# ZYNQ_JTAG_and_Decoupling.net
KiCad netlist of a schematic drawn in Altium Designer
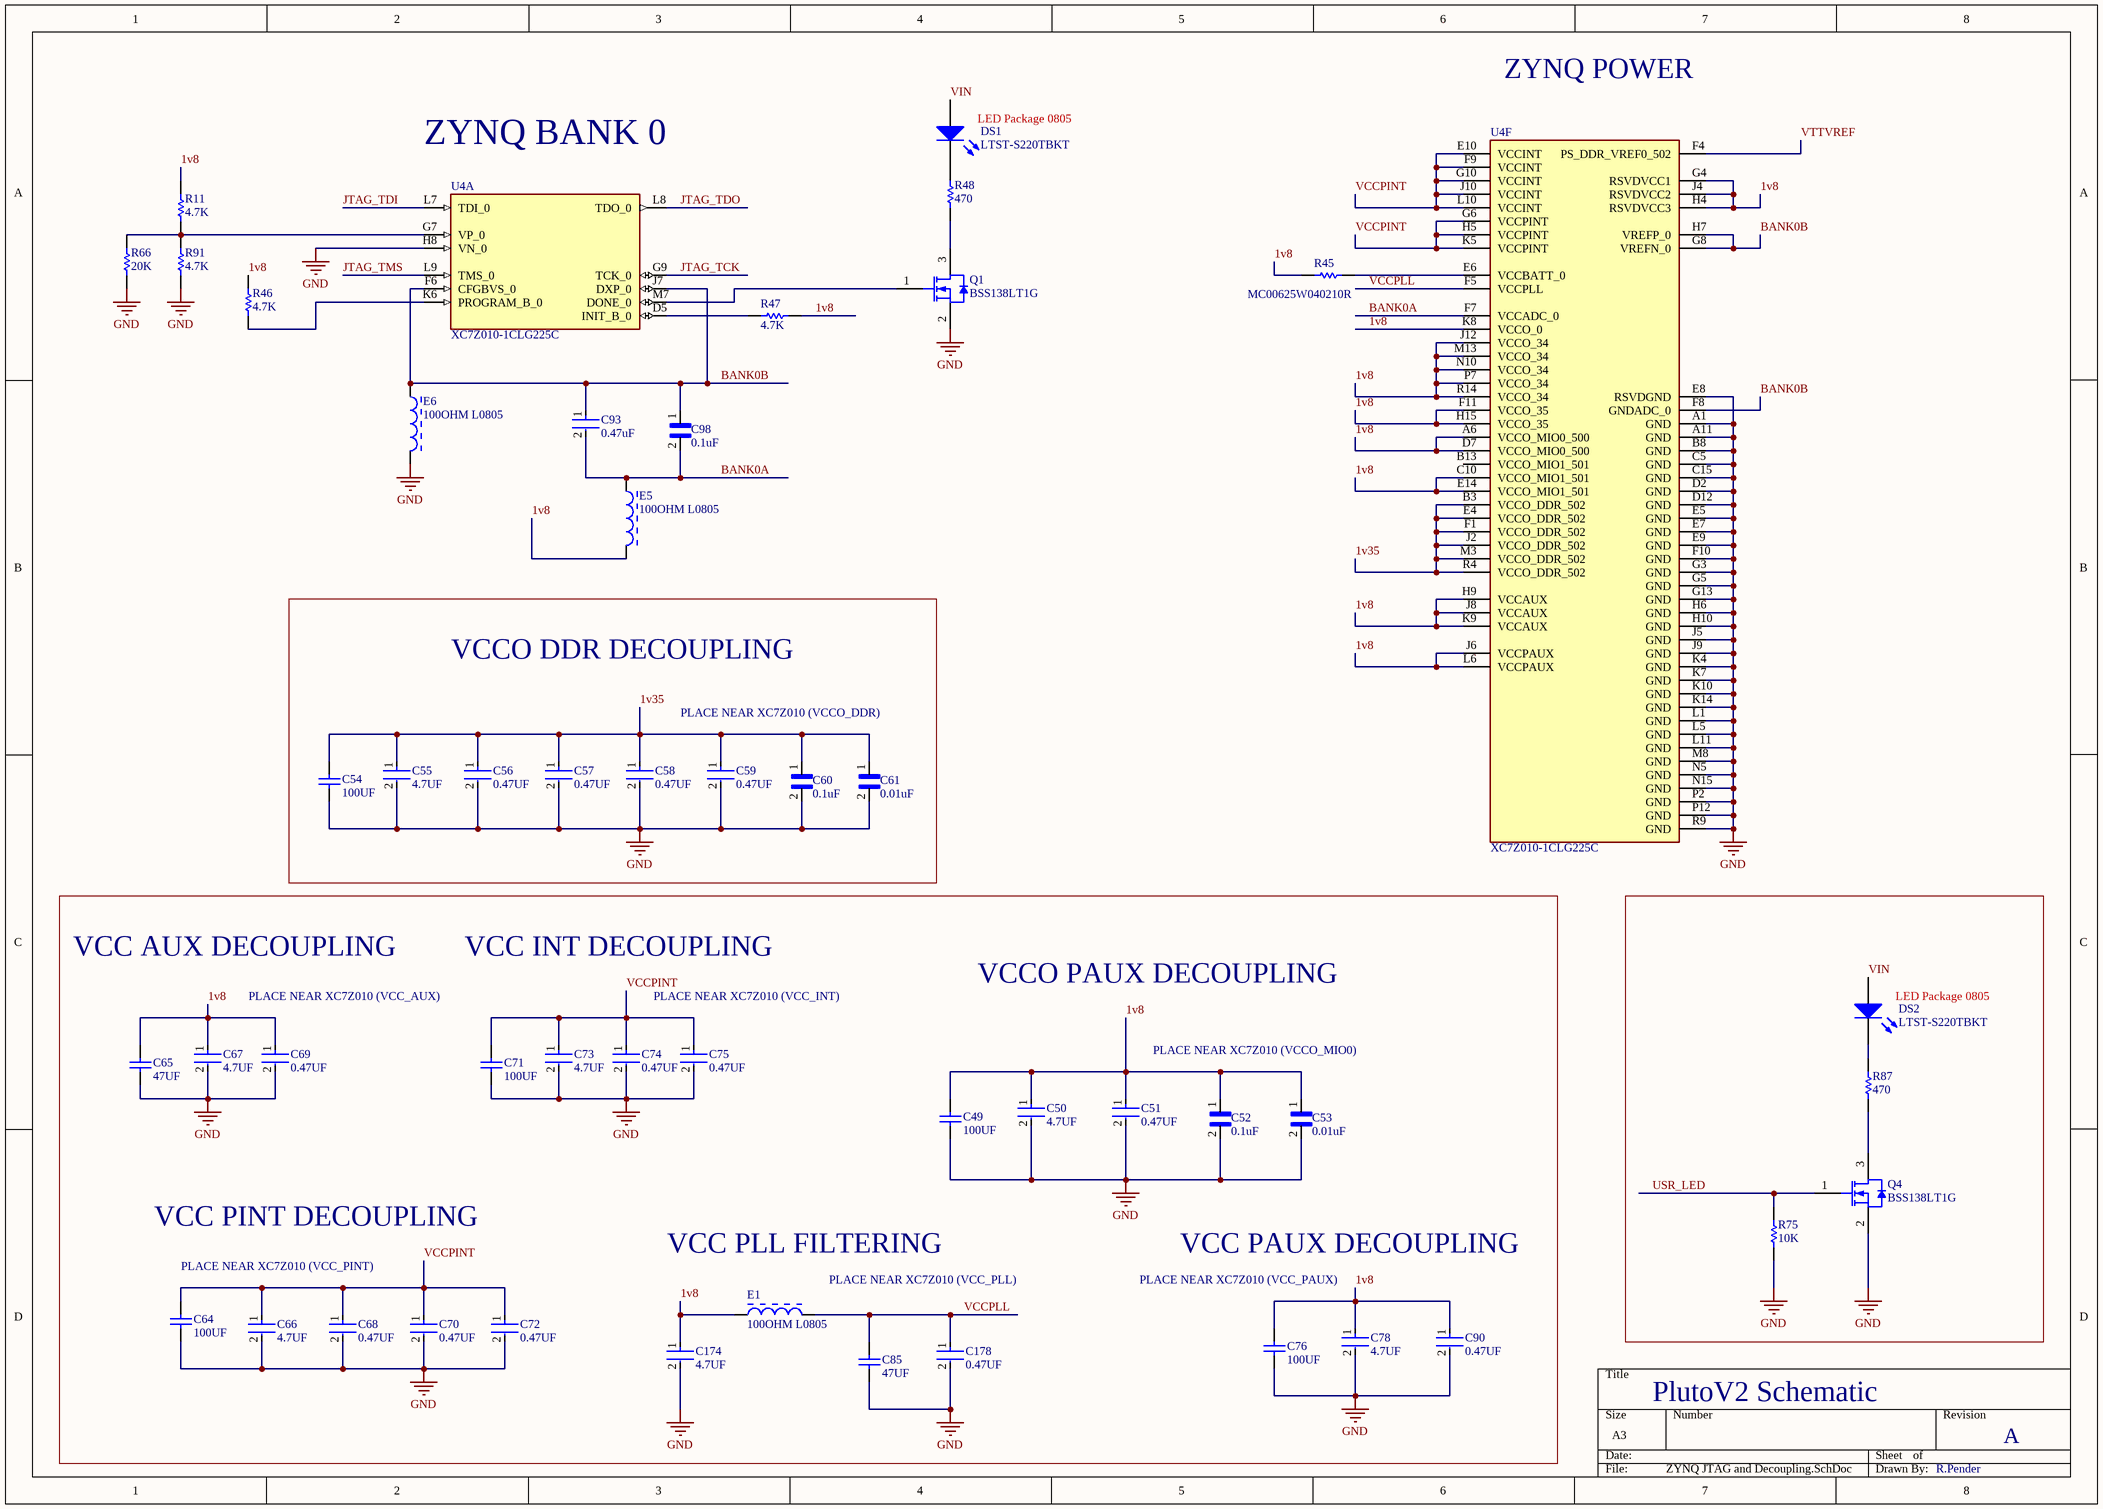
[diagram p0: ZYNQ JTAG and Decoupling.SchDoc]

(export (version "E")
  (design (tool "Eeschema 10.0.6"))
  (components
    (comp (ref "C49")
      (value "100UF")
      (footprint "CAPC3216X190X55ML30T25")
      (description "Chip Capacitor, 100 uF, +/- 20%, 6.3 V, -55 to 85 degC, 1206 (3216 Metric), RoHS, Tape and Reel")
      (fields (field (name "TOLERANCE") "20%") (field (name "PARTNUMBER") "GRM31CR60J107ME39L"))
      (libsource (lib "Altium Content Vault") (part "CAP-NP-2"))
    )
    (comp (ref "C50")
      (value "4.7UF")
      (footprint "FP-C1005-050-0_15-MFG")
      (description "CAP CER 4.7UF 6.3V X5R 0402")
      (fields (field (name "VOLTAGE") "6.3V") (field (name "TOLERANCE") "10%"))
      (libsource (lib "Altium Content Vault") (part "02cd4be3c70576c341d710602a673aa"))
    )
    (comp (ref "C51")
      (value "0.47UF")
      (footprint "FP-C1005-050-0_15-MFG")
      (description "CAP CER 4.7UF 6.3V X5R 0402")
      (fields (field (name "VOLTAGE") "6.3V") (field (name "TOLERANCE") "10%"))
      (libsource (lib "Altium Content Vault") (part "02cd4be3c70576c341d710602a673aa"))
    )
    (comp (ref "C52")
      (value "0.1uF")
      (footprint "CAPC0603X33N")
      (description "CAP 0.1UF 16VDC X5R 20% SMD 0201 PAPER TAPE")
      (fields (field (name "MP") "GRM033R61C104ME84D"))
      (libsource (lib "GRM033R61C104ME84D") (part "GRM033R61C104ME84D"))
    )
    (comp (ref "C53")
      (value "0.01uF")
      (footprint "CAPC0603X33N")
      (description "SMD Capacitor X7R(EIA) with Capacitance: 10000pF Tol. 10%. Rated Voltage: 10Vdc")
      (fields (field (name "MP") "GRM033R71A103KA01D") (field (name "MF") "Murata"))
      (libsource (lib "GRM033R71A103KA01D") (part "GRM033R71A103KA01D"))
    )
    (comp (ref "C54")
      (value "100UF")
      (footprint "CAPC3216X190X55ML30T25")
      (description "Chip Capacitor, 100 uF, +/- 20%, 6.3 V, -55 to 85 degC, 1206 (3216 Metric), RoHS, Tape and Reel")
      (fields (field (name "TOLERANCE") "20%") (field (name "PARTNUMBER") "GRM31CR60J107ME39L"))
      (libsource (lib "Altium Content Vault") (part "CAP-NP-2"))
    )
    (comp (ref "C55")
      (value "4.7UF")
      (footprint "FP-C1005-050-0_15-MFG")
      (description "CAP CER 4.7UF 6.3V X5R 0402")
      (fields (field (name "VOLTAGE") "6.3V") (field (name "TOLERANCE") "10%"))
      (libsource (lib "Altium Content Vault") (part "02cd4be3c70576c341d710602a673aa"))
    )
    (comp (ref "C56")
      (value "0.47UF")
      (footprint "FP-C1005-050-0_15-MFG")
      (description "CAP CER 4.7UF 6.3V X5R 0402")
      (fields (field (name "VOLTAGE") "6.3V") (field (name "TOLERANCE") "10%"))
      (libsource (lib "Altium Content Vault") (part "02cd4be3c70576c341d710602a673aa"))
    )
    (comp (ref "C57")
      (value "0.47UF")
      (footprint "FP-C1005-050-0_15-MFG")
      (description "CAP CER 4.7UF 6.3V X5R 0402")
      (fields (field (name "VOLTAGE") "6.3V") (field (name "TOLERANCE") "10%"))
      (libsource (lib "Altium Content Vault") (part "02cd4be3c70576c341d710602a673aa"))
    )
    (comp (ref "C58")
      (value "0.47UF")
      (footprint "FP-C1005-050-0_15-MFG")
      (description "CAP CER 4.7UF 6.3V X5R 0402")
      (fields (field (name "VOLTAGE") "6.3V") (field (name "TOLERANCE") "10%"))
      (libsource (lib "Altium Content Vault") (part "02cd4be3c70576c341d710602a673aa"))
    )
    (comp (ref "C59")
      (value "0.47UF")
      (footprint "FP-C1005-050-0_15-MFG")
      (description "CAP CER 4.7UF 6.3V X5R 0402")
      (fields (field (name "VOLTAGE") "6.3V") (field (name "TOLERANCE") "10%"))
      (libsource (lib "Altium Content Vault") (part "02cd4be3c70576c341d710602a673aa"))
    )
    (comp (ref "C60")
      (value "0.1uF")
      (footprint "CAPC0603X33N")
      (description "CAP 0.1UF 16VDC X5R 20% SMD 0201 PAPER TAPE")
      (fields (field (name "MP") "GRM033R61C104ME84D"))
      (libsource (lib "GRM033R61C104ME84D") (part "GRM033R61C104ME84D"))
    )
    (comp (ref "C61")
      (value "0.01uF")
      (footprint "CAPC0603X33N")
      (description "SMD Capacitor X7R(EIA) with Capacitance: 10000pF Tol. 10%. Rated Voltage: 10Vdc")
      (fields (field (name "MP") "GRM033R71A103KA01D") (field (name "MF") "Murata"))
      (libsource (lib "GRM033R71A103KA01D") (part "GRM033R71A103KA01D"))
    )
    (comp (ref "C64")
      (value "100UF")
      (footprint "CAPC3216X190X55ML30T25")
      (description "Chip Capacitor, 100 uF, +/- 20%, 6.3 V, -55 to 85 degC, 1206 (3216 Metric), RoHS, Tape and Reel")
      (fields (field (name "TOLERANCE") "20%") (field (name "PARTNUMBER") "GRM31CR60J107ME39L"))
      (libsource (lib "Altium Content Vault") (part "CAP-NP-2"))
    )
    (comp (ref "C65")
      (value "47UF")
      (footprint "TAYO-JMK212BBJ476MG-T_L")
      (fields
        (field (name "MANUFACTURER") "Taiyo Yuden")
        (field (name "TOLERANCE") "±20%")
        (field (name "PCN PART NUMBER") "X5R,X7RDielectrics23/Jan/2008")
      )
      (libsource (lib "Altium Content Vault") (part "CAP-NP-2"))
    )
    (comp (ref "C66")
      (value "4.7UF")
      (footprint "FP-C1005-050-0_15-MFG")
      (description "CAP CER 4.7UF 6.3V X5R 0402")
      (fields (field (name "VOLTAGE") "6.3V") (field (name "TOLERANCE") "10%"))
      (libsource (lib "Altium Content Vault") (part "02cd4be3c70576c341d710602a673aa"))
    )
    (comp (ref "C67")
      (value "4.7UF")
      (footprint "FP-C1005-050-0_15-MFG")
      (description "CAP CER 4.7UF 6.3V X5R 0402")
      (fields (field (name "VOLTAGE") "6.3V") (field (name "TOLERANCE") "10%"))
      (libsource (lib "Altium Content Vault") (part "02cd4be3c70576c341d710602a673aa"))
    )
    (comp (ref "C68")
      (value "0.47UF")
      (footprint "FP-C1005-050-0_15-MFG")
      (description "CAP CER 4.7UF 6.3V X5R 0402")
      (fields (field (name "VOLTAGE") "6.3V") (field (name "TOLERANCE") "10%"))
      (libsource (lib "Altium Content Vault") (part "02cd4be3c70576c341d710602a673aa"))
    )
    (comp (ref "C69")
      (value "0.47UF")
      (footprint "FP-C1005-050-0_15-MFG")
      (description "CAP CER 4.7UF 6.3V X5R 0402")
      (fields (field (name "VOLTAGE") "6.3V") (field (name "TOLERANCE") "10%"))
      (libsource (lib "Altium Content Vault") (part "02cd4be3c70576c341d710602a673aa"))
    )
    (comp (ref "C70")
      (value "0.47UF")
      (footprint "FP-C1005-050-0_15-MFG")
      (description "CAP CER 4.7UF 6.3V X5R 0402")
      (fields (field (name "VOLTAGE") "6.3V") (field (name "TOLERANCE") "10%"))
      (libsource (lib "Altium Content Vault") (part "02cd4be3c70576c341d710602a673aa"))
    )
    (comp (ref "C71")
      (value "100UF")
      (footprint "CAPC3216X190X55ML30T25")
      (description "Chip Capacitor, 100 uF, +/- 20%, 6.3 V, -55 to 85 degC, 1206 (3216 Metric), RoHS, Tape and Reel")
      (fields (field (name "TOLERANCE") "20%") (field (name "PARTNUMBER") "GRM31CR60J107ME39L"))
      (libsource (lib "Altium Content Vault") (part "CAP-NP-2"))
    )
    (comp (ref "C72")
      (value "0.47UF")
      (footprint "FP-C1005-050-0_15-MFG")
      (description "CAP CER 4.7UF 6.3V X5R 0402")
      (fields (field (name "VOLTAGE") "6.3V") (field (name "TOLERANCE") "10%"))
      (libsource (lib "Altium Content Vault") (part "02cd4be3c70576c341d710602a673aa"))
    )
    (comp (ref "C73")
      (value "4.7UF")
      (footprint "FP-C1005-050-0_15-MFG")
      (description "CAP CER 4.7UF 6.3V X5R 0402")
      (fields (field (name "VOLTAGE") "6.3V") (field (name "TOLERANCE") "10%"))
      (libsource (lib "Altium Content Vault") (part "02cd4be3c70576c341d710602a673aa"))
    )
    (comp (ref "C74")
      (value "0.47UF")
      (footprint "FP-C1005-050-0_15-MFG")
      (description "CAP CER 4.7UF 6.3V X5R 0402")
      (fields (field (name "VOLTAGE") "6.3V") (field (name "TOLERANCE") "10%"))
      (libsource (lib "Altium Content Vault") (part "02cd4be3c70576c341d710602a673aa"))
    )
    (comp (ref "C75")
      (value "0.47UF")
      (footprint "FP-C1005-050-0_15-MFG")
      (description "CAP CER 4.7UF 6.3V X5R 0402")
      (fields (field (name "VOLTAGE") "6.3V") (field (name "TOLERANCE") "10%"))
      (libsource (lib "Altium Content Vault") (part "02cd4be3c70576c341d710602a673aa"))
    )
    (comp (ref "C76")
      (value "100UF")
      (footprint "CAPC3216X190X55ML30T25")
      (description "Chip Capacitor, 100 uF, +/- 20%, 6.3 V, -55 to 85 degC, 1206 (3216 Metric), RoHS, Tape and Reel")
      (fields (field (name "TOLERANCE") "20%") (field (name "PARTNUMBER") "GRM31CR60J107ME39L"))
      (libsource (lib "Altium Content Vault") (part "CAP-NP-2"))
    )
    (comp (ref "C78")
      (value "4.7UF")
      (footprint "FP-C1005-050-0_15-MFG")
      (description "CAP CER 4.7UF 6.3V X5R 0402")
      (fields (field (name "VOLTAGE") "6.3V") (field (name "TOLERANCE") "10%"))
      (libsource (lib "Altium Content Vault") (part "02cd4be3c70576c341d710602a673aa"))
    )
    (comp (ref "C85")
      (value "47UF")
      (footprint "TAYO-JMK212BBJ476MG-T_L")
      (fields
        (field (name "MANUFACTURER") "Taiyo Yuden")
        (field (name "TOLERANCE") "±20%")
        (field (name "PCN PART NUMBER") "X5R,X7RDielectrics23/Jan/2008")
      )
      (libsource (lib "Altium Content Vault") (part "CAP-NP-2"))
    )
    (comp (ref "C90")
      (value "0.47UF")
      (footprint "FP-C1005-050-0_15-MFG")
      (description "CAP CER 4.7UF 6.3V X5R 0402")
      (fields (field (name "VOLTAGE") "6.3V") (field (name "TOLERANCE") "10%"))
      (libsource (lib "Altium Content Vault") (part "02cd4be3c70576c341d710602a673aa"))
    )
    (comp (ref "C93")
      (value "0.47uF")
      (footprint "FP-C1005-050-0_15-MFG")
      (description "CAP CER 4.7UF 6.3V X5R 0402")
      (fields (field (name "VOLTAGE") "6.3V") (field (name "TOLERANCE") "10%"))
      (libsource (lib "Altium Content Vault") (part "02cd4be3c70576c341d710602a673aa"))
    )
    (comp (ref "C98")
      (value "0.1uF")
      (footprint "CAPC0603X33N")
      (description "CAP 0.1UF 16VDC X5R 20% SMD 0201 PAPER TAPE")
      (fields (field (name "MP") "GRM033R61C104ME84D"))
      (libsource (lib "GRM033R61C104ME84D") (part "GRM033R61C104ME84D"))
    )
    (comp (ref "C174")
      (value "4.7UF")
      (footprint "FP-C1005-050-0_15-MFG")
      (description "CAP CER 4.7UF 6.3V X5R 0402")
      (fields (field (name "VOLTAGE") "6.3V") (field (name "TOLERANCE") "10%"))
      (libsource (lib "Altium Content Vault") (part "02cd4be3c70576c341d710602a673aa"))
    )
    (comp (ref "C178")
      (value "0.47UF")
      (footprint "FP-C1005-050-0_15-MFG")
      (description "CAP CER 4.7UF 6.3V X5R 0402")
      (fields (field (name "VOLTAGE") "6.3V") (field (name "TOLERANCE") "10%"))
      (libsource (lib "Altium Content Vault") (part "02cd4be3c70576c341d710602a673aa"))
    )
    (comp (ref "DS1")
      (value "LTST-S220TBKT")
      (footprint "CAPC2012X94N")
      (description "Typical BLUE SiC LED")
      (fields (field (name "PUBLISHER") "Altium Limited"))
      (libsource (lib "Miscellaneous Devices") (part "LED3"))
    )
    (comp (ref "DS2")
      (value "LTST-S220TBKT")
      (footprint "CAPC2012X94N")
      (description "Typical BLUE SiC LED")
      (fields (field (name "PUBLISHER") "Altium Limited"))
      (libsource (lib "Miscellaneous Devices") (part "LED3"))
    )
    (comp (ref "E1")
      (value "100OHM L0805")
      (footprint "TDK-MPZ2012S101A-2_V")
      (fields (field (name "TOLERANCE") "25%") (field (name "MANUFACTURER") "TDK"))
      (libsource (lib "Altium Content Vault") (part "BEAD-2"))
    )
    (comp (ref "E5")
      (value "100OHM L0805")
      (footprint "TDK-MPZ2012S101A-2_V")
      (fields (field (name "TOLERANCE") "25%") (field (name "MANUFACTURER") "TDK"))
      (libsource (lib "Altium Content Vault") (part "BEAD-2"))
    )
    (comp (ref "E6")
      (value "100OHM L0805")
      (footprint "TDK-MPZ2012S101A-2_V")
      (fields (field (name "TOLERANCE") "25%") (field (name "MANUFACTURER") "TDK"))
      (libsource (lib "Altium Content Vault") (part "BEAD-2"))
    )
    (comp (ref "Q1")
      (value "BSS138LT1G")
      (footprint "ONSC-SOT-23-3-318-08_V")
      (description "Power MOSFET, 200 mA, 50 V, N-Channel, 3-Pin SOT-23, Pb-Free, Tape and Reel")
      (fields (field (name "MANUFACTURER") "On Semiconductor"))
      (libsource (lib "Altium Content Vault") (part "ONSC-NMOS-G1S2D3-3"))
    )
    (comp (ref "Q4")
      (value "BSS138LT1G")
      (footprint "ONSC-SOT-23-3-318-08_V")
      (description "Power MOSFET, 200 mA, 50 V, N-Channel, 3-Pin SOT-23, Pb-Free, Tape and Reel")
      (fields (field (name "MANUFACTURER") "On Semiconductor"))
      (libsource (lib "Altium Content Vault") (part "ONSC-NMOS-G1S2D3-3"))
    )
    (comp (ref "R11")
      (value "4.7K")
      (footprint "2-0402")
      (fields (field (name "PUBLISHER") "Altium Limited"))
      (libsource (lib "Panasonic Resistor") (part "ERJ2RK"))
    )
    (comp (ref "R45")
      (value "MC00625W040210R")
      (footprint "RESC1005X40X25NL10T10")
      (fields (field (name "MANUFACTURER") "Multicomp"))
      (libsource (lib "Altium Content Vault") (part "RES"))
    )
    (comp (ref "R46")
      (value "4.7K")
      (footprint "2-0402")
      (fields (field (name "PUBLISHER") "Altium Limited"))
      (libsource (lib "Panasonic Resistor") (part "ERJ2RK"))
    )
    (comp (ref "R47")
      (value "4.7K")
      (footprint "2-0402")
      (fields (field (name "PUBLISHER") "Altium Limited"))
      (libsource (lib "Panasonic Resistor") (part "ERJ2RK"))
    )
    (comp (ref "R48")
      (value "470")
      (footprint "2-0402")
      (description "Thick Film Chip Resistor, 1 Ohm to 2.2M Ohm Range, 5% Tolerance, 0402 Size, 0.063 W")
      (fields (field (name "PUBLISHER") "Altium Limited"))
      (libsource (lib "Panasonic Resistor") (part "ERJ2GE"))
    )
    (comp (ref "R66")
      (value "20K")
      (footprint "2-0402")
      (fields (field (name "PUBLISHER") "Altium Limited"))
      (libsource (lib "Panasonic Resistor") (part "ERJ2RK"))
    )
    (comp (ref "R75")
      (value "10K")
      (footprint "2-0402")
      (fields (field (name "PUBLISHER") "Altium Limited"))
      (libsource (lib "Panasonic Resistor") (part "ERJ2RK"))
    )
    (comp (ref "R87")
      (value "470")
      (footprint "2-0402")
      (description "Thick Film Chip Resistor, 1 Ohm to 2.2M Ohm Range, 5% Tolerance, 0402 Size, 0.063 W")
      (fields (field (name "PUBLISHER") "Altium Limited"))
      (libsource (lib "Panasonic Resistor") (part "ERJ2GE"))
    )
    (comp (ref "R91")
      (value "4.7K")
      (footprint "2-0402")
      (fields (field (name "PUBLISHER") "Altium Limited"))
      (libsource (lib "Panasonic Resistor") (part "ERJ2RK"))
    )
    (comp (ref "U4")
      (value "XC7Z010-1CLG225C")
      (footprint "BGA225C80P15X15_1300X1300X150")
      (fields (field (name "MF") "Xilinx Inc.") (field (name "DIGI-KEY_PART_NUMBER") "122-1855-ND"))
      (libsource (lib "XC7Z010-1CLG225C") (part "XC7Z010-1CLG225C"))
    )
  )
  (nets
    (net (code "1") (name "/1v8") (class "Default")
      (node (ref "C174") (pin "1") (pinfunction "1_1") (pintype "passive"))
      (node (ref "C49") (pin "1") (pinfunction "1_1") (pintype "passive"))
      (node (ref "C50") (pin "1") (pinfunction "1_1") (pintype "passive"))
      (node (ref "C51") (pin "1") (pinfunction "1_1") (pintype "passive"))
      (node (ref "C52") (pin "1") (pinfunction "1_1") (pintype "passive"))
      (node (ref "C53") (pin "1") (pinfunction "1_1") (pintype "passive"))
      (node (ref "C65") (pin "1") (pinfunction "1_1") (pintype "passive"))
      (node (ref "C67") (pin "1") (pinfunction "1_1") (pintype "passive"))
      (node (ref "C69") (pin "1") (pinfunction "1_1") (pintype "passive"))
      (node (ref "C76") (pin "1") (pinfunction "1_1") (pintype "passive"))
      (node (ref "C78") (pin "1") (pinfunction "1_1") (pintype "passive"))
      (node (ref "C90") (pin "1") (pinfunction "1_1") (pintype "passive"))
      (node (ref "E1") (pin "1") (pinfunction "1_1") (pintype "passive"))
      (node (ref "E5") (pin "2") (pinfunction "2_2") (pintype "passive"))
      (node (ref "R11") (pin "1") (pinfunction "1_1") (pintype "passive"))
      (node (ref "R45") (pin "1") (pinfunction "1_1") (pintype "passive"))
      (node (ref "R46") (pin "1") (pinfunction "1_1") (pintype "passive"))
      (node (ref "R47") (pin "1") (pinfunction "1_1") (pintype "passive"))
      (node (ref "U4") (pin "A6") (pinfunction "VCCO_MIO0_500_A6") (pintype "power_in"))
      (node (ref "U4") (pin "C10") (pinfunction "VCCO_MIO1_501_C10") (pintype "power_in"))
      (node (ref "U4") (pin "D7") (pinfunction "VCCO_MIO0_500_D7") (pintype "power_in"))
      (node (ref "U4") (pin "E14") (pinfunction "VCCO_MIO1_501_E14") (pintype "power_in"))
      (node (ref "U4") (pin "F11") (pinfunction "VCCO_35_F11") (pintype "power_in"))
      (node (ref "U4") (pin "G4") (pinfunction "RSVDVCC1_G4") (pintype "power_in"))
      (node (ref "U4") (pin "H15") (pinfunction "VCCO_35_H15") (pintype "power_in"))
      (node (ref "U4") (pin "H4") (pinfunction "RSVDVCC3_H4") (pintype "power_in"))
      (node (ref "U4") (pin "H9") (pinfunction "VCCAUX_H9") (pintype "power_in"))
      (node (ref "U4") (pin "J12") (pinfunction "VCCO_34_J12") (pintype "power_in"))
      (node (ref "U4") (pin "J4") (pinfunction "RSVDVCC2_J4") (pintype "power_in"))
      (node (ref "U4") (pin "J6") (pinfunction "VCCPAUX_J6") (pintype "power_in"))
      (node (ref "U4") (pin "J8") (pinfunction "VCCAUX_J8") (pintype "power_in"))
      (node (ref "U4") (pin "K8") (pinfunction "VCCO_0_K8") (pintype "power_in"))
      (node (ref "U4") (pin "K9") (pinfunction "VCCAUX_K9") (pintype "power_in"))
      (node (ref "U4") (pin "L6") (pinfunction "VCCPAUX_L6") (pintype "power_in"))
      (node (ref "U4") (pin "M13") (pinfunction "VCCO_34_M13") (pintype "power_in"))
      (node (ref "U4") (pin "N10") (pinfunction "VCCO_34_N10") (pintype "power_in"))
      (node (ref "U4") (pin "P7") (pinfunction "VCCO_34_P7") (pintype "power_in"))
      (node (ref "U4") (pin "R14") (pinfunction "VCCO_34_R14") (pintype "power_in"))
    )
    (net (code "2") (name "/1v35") (class "Default")
      (node (ref "C54") (pin "2") (pinfunction "2_2") (pintype "passive"))
      (node (ref "C55") (pin "1") (pinfunction "1_1") (pintype "passive"))
      (node (ref "C56") (pin "1") (pinfunction "1_1") (pintype "passive"))
      (node (ref "C57") (pin "1") (pinfunction "1_1") (pintype "passive"))
      (node (ref "C58") (pin "1") (pinfunction "1_1") (pintype "passive"))
      (node (ref "C59") (pin "1") (pinfunction "1_1") (pintype "passive"))
      (node (ref "C60") (pin "1") (pinfunction "1_1") (pintype "passive"))
      (node (ref "C61") (pin "1") (pinfunction "1_1") (pintype "passive"))
      (node (ref "U4") (pin "B3") (pinfunction "VCCO_DDR_502_B3") (pintype "power_in"))
      (node (ref "U4") (pin "E4") (pinfunction "VCCO_DDR_502_E4") (pintype "power_in"))
      (node (ref "U4") (pin "F1") (pinfunction "VCCO_DDR_502_F1") (pintype "power_in"))
      (node (ref "U4") (pin "J2") (pinfunction "VCCO_DDR_502_J2") (pintype "power_in"))
      (node (ref "U4") (pin "M3") (pinfunction "VCCO_DDR_502_M3") (pintype "power_in"))
      (node (ref "U4") (pin "R4") (pinfunction "VCCO_DDR_502_R4") (pintype "power_in"))
    )
    (net (code "3") (name "/BANK0A") (class "Default")
      (node (ref "C93") (pin "2") (pinfunction "2_2") (pintype "passive"))
      (node (ref "C98") (pin "2") (pinfunction "2_2") (pintype "passive"))
      (node (ref "E5") (pin "1") (pinfunction "1_1") (pintype "passive"))
      (node (ref "U4") (pin "F7") (pinfunction "VCCADC_0_F7") (pintype "power_in"))
    )
    (net (code "4") (name "/BANK0B") (class "Default")
      (node (ref "C93") (pin "1") (pinfunction "1_1") (pintype "passive"))
      (node (ref "C98") (pin "1") (pinfunction "1_1") (pintype "passive"))
      (node (ref "E6") (pin "1") (pinfunction "1_1") (pintype "passive"))
      (node (ref "U4") (pin "F6") (pinfunction "CFGBVS_0_F6") (pintype "input"))
      (node (ref "U4") (pin "F8") (pinfunction "GNDADC_0_F8") (pintype "power_in"))
      (node (ref "U4") (pin "G8") (pinfunction "VREFN_0_G8") (pintype "power_in"))
      (node (ref "U4") (pin "H7") (pinfunction "VREFP_0_H7") (pintype "power_in"))
      (node (ref "U4") (pin "J7") (pinfunction "DXP_0_J7") (pintype "bidirectional"))
    )
    (net (code "5") (name "/JTAG_TCK") (class "Default")
      (node (ref "U4") (pin "G9") (pinfunction "TCK_0_G9") (pintype "bidirectional"))
    )
    (net (code "6") (name "/JTAG_TDI") (class "Default")
      (node (ref "U4") (pin "L7") (pinfunction "TDI_0_L7") (pintype "input"))
    )
    (net (code "7") (name "/JTAG_TDO") (class "Default")
      (node (ref "U4") (pin "L8") (pinfunction "TDO_0_L8") (pintype "output"))
    )
    (net (code "8") (name "/JTAG_TMS") (class "Default")
      (node (ref "U4") (pin "L9") (pinfunction "TMS_0_L9") (pintype "input"))
    )
    (net (code "9") (name "/USR_LED") (class "Default")
      (node (ref "Q4") (pin "1") (pinfunction "G_1") (pintype "passive"))
      (node (ref "R75") (pin "1") (pinfunction "1_1") (pintype "passive"))
    )
    (net (code "10") (name "/VCCPINT") (class "Default")
      (node (ref "C64") (pin "2") (pinfunction "2_2") (pintype "passive"))
      (node (ref "C66") (pin "1") (pinfunction "1_1") (pintype "passive"))
      (node (ref "C68") (pin "1") (pinfunction "1_1") (pintype "passive"))
      (node (ref "C70") (pin "1") (pinfunction "1_1") (pintype "passive"))
      (node (ref "C71") (pin "2") (pinfunction "2_2") (pintype "passive"))
      (node (ref "C72") (pin "1") (pinfunction "1_1") (pintype "passive"))
      (node (ref "C73") (pin "1") (pinfunction "1_1") (pintype "passive"))
      (node (ref "C74") (pin "1") (pinfunction "1_1") (pintype "passive"))
      (node (ref "C75") (pin "1") (pinfunction "1_1") (pintype "passive"))
      (node (ref "U4") (pin "E10") (pinfunction "VCCINT_E10") (pintype "power_in"))
      (node (ref "U4") (pin "F9") (pinfunction "VCCINT_F9") (pintype "power_in"))
      (node (ref "U4") (pin "G10") (pinfunction "VCCINT_G10") (pintype "power_in"))
      (node (ref "U4") (pin "G6") (pinfunction "VCCPINT_G6") (pintype "power_in"))
      (node (ref "U4") (pin "H5") (pinfunction "VCCPINT_H5") (pintype "power_in"))
      (node (ref "U4") (pin "J10") (pinfunction "VCCINT_J10") (pintype "power_in"))
      (node (ref "U4") (pin "K5") (pinfunction "VCCPINT_K5") (pintype "power_in"))
      (node (ref "U4") (pin "L10") (pinfunction "VCCINT_L10") (pintype "power_in"))
    )
    (net (code "11") (name "/VCCPLL") (class "Default")
      (node (ref "C178") (pin "1") (pinfunction "1_1") (pintype "passive"))
      (node (ref "C85") (pin "2") (pinfunction "2_2") (pintype "passive"))
      (node (ref "E1") (pin "2") (pinfunction "2_2") (pintype "passive"))
      (node (ref "U4") (pin "F5") (pinfunction "VCCPLL_F5") (pintype "power_in"))
    )
    (net (code "12") (name "/VIN") (class "Default")
      (node (ref "DS1") (pin "1") (pinfunction "A_1") (pintype "passive"))
      (node (ref "DS2") (pin "1") (pinfunction "A_1") (pintype "passive"))
    )
    (net (code "13") (name "/VTTVREF") (class "Default")
      (node (ref "U4") (pin "F4") (pinfunction "PS_DDR_VREF0_502_F4") (pintype "power_in"))
    )
    (net (code "14") (name "GND") (class "Default")
      (node (ref "C174") (pin "2") (pinfunction "2_2") (pintype "passive"))
      (node (ref "C178") (pin "2") (pinfunction "2_2") (pintype "passive"))
      (node (ref "C49") (pin "2") (pinfunction "2_2") (pintype "passive"))
      (node (ref "C50") (pin "2") (pinfunction "2_2") (pintype "passive"))
      (node (ref "C51") (pin "2") (pinfunction "2_2") (pintype "passive"))
      (node (ref "C52") (pin "2") (pinfunction "2_2") (pintype "passive"))
      (node (ref "C53") (pin "2") (pinfunction "2_2") (pintype "passive"))
      (node (ref "C54") (pin "1") (pinfunction "1_1") (pintype "passive"))
      (node (ref "C55") (pin "2") (pinfunction "2_2") (pintype "passive"))
      (node (ref "C56") (pin "2") (pinfunction "2_2") (pintype "passive"))
      (node (ref "C57") (pin "2") (pinfunction "2_2") (pintype "passive"))
      (node (ref "C58") (pin "2") (pinfunction "2_2") (pintype "passive"))
      (node (ref "C59") (pin "2") (pinfunction "2_2") (pintype "passive"))
      (node (ref "C60") (pin "2") (pinfunction "2_2") (pintype "passive"))
      (node (ref "C61") (pin "2") (pinfunction "2_2") (pintype "passive"))
      (node (ref "C64") (pin "1") (pinfunction "1_1") (pintype "passive"))
      (node (ref "C65") (pin "2") (pinfunction "2_2") (pintype "passive"))
      (node (ref "C66") (pin "2") (pinfunction "2_2") (pintype "passive"))
      (node (ref "C67") (pin "2") (pinfunction "2_2") (pintype "passive"))
      (node (ref "C68") (pin "2") (pinfunction "2_2") (pintype "passive"))
      (node (ref "C69") (pin "2") (pinfunction "2_2") (pintype "passive"))
      (node (ref "C70") (pin "2") (pinfunction "2_2") (pintype "passive"))
      (node (ref "C71") (pin "1") (pinfunction "1_1") (pintype "passive"))
      (node (ref "C72") (pin "2") (pinfunction "2_2") (pintype "passive"))
      (node (ref "C73") (pin "2") (pinfunction "2_2") (pintype "passive"))
      (node (ref "C74") (pin "2") (pinfunction "2_2") (pintype "passive"))
      (node (ref "C75") (pin "2") (pinfunction "2_2") (pintype "passive"))
      (node (ref "C76") (pin "2") (pinfunction "2_2") (pintype "passive"))
      (node (ref "C78") (pin "2") (pinfunction "2_2") (pintype "passive"))
      (node (ref "C85") (pin "1") (pinfunction "1_1") (pintype "passive"))
      (node (ref "C90") (pin "2") (pinfunction "2_2") (pintype "passive"))
      (node (ref "E6") (pin "2") (pinfunction "2_2") (pintype "passive"))
      (node (ref "Q1") (pin "2") (pinfunction "S_2") (pintype "passive"))
      (node (ref "Q4") (pin "2") (pinfunction "S_2") (pintype "passive"))
      (node (ref "R66") (pin "2") (pinfunction "2_2") (pintype "passive"))
      (node (ref "R75") (pin "2") (pinfunction "2_2") (pintype "passive"))
      (node (ref "R91") (pin "2") (pinfunction "2_2") (pintype "passive"))
      (node (ref "U4") (pin "A1") (pinfunction "GND_A1") (pintype "power_in"))
      (node (ref "U4") (pin "A11") (pinfunction "GND_A11") (pintype "power_in"))
      (node (ref "U4") (pin "B8") (pinfunction "GND_B8") (pintype "power_in"))
      (node (ref "U4") (pin "C15") (pinfunction "GND_C15") (pintype "power_in"))
      (node (ref "U4") (pin "C5") (pinfunction "GND_C5") (pintype "power_in"))
      (node (ref "U4") (pin "D12") (pinfunction "GND_D12") (pintype "power_in"))
      (node (ref "U4") (pin "D2") (pinfunction "GND_D2") (pintype "power_in"))
      (node (ref "U4") (pin "E5") (pinfunction "GND_E5") (pintype "power_in"))
      (node (ref "U4") (pin "E7") (pinfunction "GND_E7") (pintype "power_in"))
      (node (ref "U4") (pin "E8") (pinfunction "RSVDGND_E8") (pintype "power_in"))
      (node (ref "U4") (pin "E9") (pinfunction "GND_E9") (pintype "power_in"))
      (node (ref "U4") (pin "F10") (pinfunction "GND_F10") (pintype "power_in"))
      (node (ref "U4") (pin "G13") (pinfunction "GND_G13") (pintype "power_in"))
      (node (ref "U4") (pin "G3") (pinfunction "GND_G3") (pintype "power_in"))
      (node (ref "U4") (pin "G5") (pinfunction "GND_G5") (pintype "power_in"))
      (node (ref "U4") (pin "H10") (pinfunction "GND_H10") (pintype "power_in"))
      (node (ref "U4") (pin "H6") (pinfunction "GND_H6") (pintype "power_in"))
      (node (ref "U4") (pin "H8") (pinfunction "VN_0_H8") (pintype "input"))
      (node (ref "U4") (pin "J5") (pinfunction "GND_J5") (pintype "power_in"))
      (node (ref "U4") (pin "J9") (pinfunction "GND_J9") (pintype "power_in"))
      (node (ref "U4") (pin "K10") (pinfunction "GND_K10") (pintype "power_in"))
      (node (ref "U4") (pin "K14") (pinfunction "GND_K14") (pintype "power_in"))
      (node (ref "U4") (pin "K4") (pinfunction "GND_K4") (pintype "power_in"))
      (node (ref "U4") (pin "K7") (pinfunction "GND_K7") (pintype "power_in"))
      (node (ref "U4") (pin "L1") (pinfunction "GND_L1") (pintype "power_in"))
      (node (ref "U4") (pin "L11") (pinfunction "GND_L11") (pintype "power_in"))
      (node (ref "U4") (pin "L5") (pinfunction "GND_L5") (pintype "power_in"))
      (node (ref "U4") (pin "M8") (pinfunction "GND_M8") (pintype "power_in"))
      (node (ref "U4") (pin "N15") (pinfunction "GND_N15") (pintype "power_in"))
      (node (ref "U4") (pin "N5") (pinfunction "GND_N5") (pintype "power_in"))
      (node (ref "U4") (pin "P12") (pinfunction "GND_P12") (pintype "power_in"))
      (node (ref "U4") (pin "P2") (pinfunction "GND_P2") (pintype "power_in"))
      (node (ref "U4") (pin "R9") (pinfunction "GND_R9") (pintype "power_in"))
    )
    (net (code "15") (name "Net-(DS1-K)") (class "Default")
      (node (ref "DS1") (pin "2") (pinfunction "K_2") (pintype "passive"))
      (node (ref "R48") (pin "1") (pinfunction "1_1") (pintype "passive"))
    )
    (net (code "16") (name "Net-(DS2-K)") (class "Default")
      (node (ref "DS2") (pin "2") (pinfunction "K_2") (pintype "passive"))
      (node (ref "R87") (pin "1") (pinfunction "1_1") (pintype "passive"))
    )
    (net (code "17") (name "Net-(Q1-D)") (class "Default")
      (node (ref "Q1") (pin "3") (pinfunction "D_3") (pintype "passive"))
      (node (ref "R48") (pin "2") (pinfunction "2_2") (pintype "passive"))
    )
    (net (code "18") (name "Net-(Q1-G)") (class "Default")
      (node (ref "Q1") (pin "1") (pinfunction "G_1") (pintype "passive"))
      (node (ref "U4") (pin "M7") (pinfunction "DONE_0_M7") (pintype "bidirectional"))
    )
    (net (code "19") (name "Net-(Q4-D)") (class "Default")
      (node (ref "Q4") (pin "3") (pinfunction "D_3") (pintype "passive"))
      (node (ref "R87") (pin "2") (pinfunction "2_2") (pintype "passive"))
    )
    (net (code "20") (name "Net-(U4A-INIT_B_0)") (class "Default")
      (node (ref "R47") (pin "2") (pinfunction "2_2") (pintype "passive"))
      (node (ref "U4") (pin "D5") (pinfunction "INIT_B_0_D5") (pintype "bidirectional"))
    )
    (net (code "21") (name "Net-(U4A-PROGRAM_B_0)") (class "Default")
      (node (ref "R46") (pin "2") (pinfunction "2_2") (pintype "passive"))
      (node (ref "U4") (pin "K6") (pinfunction "PROGRAM_B_0_K6") (pintype "input"))
    )
    (net (code "22") (name "Net-(U4A-VP_0)") (class "Default")
      (node (ref "R11") (pin "2") (pinfunction "2_2") (pintype "passive"))
      (node (ref "R66") (pin "1") (pinfunction "1_1") (pintype "passive"))
      (node (ref "R91") (pin "1") (pinfunction "1_1") (pintype "passive"))
      (node (ref "U4") (pin "G7") (pinfunction "VP_0_G7") (pintype "input"))
    )
    (net (code "23") (name "Net-(U4F-VCCBATT_0)") (class "Default")
      (node (ref "R45") (pin "2") (pinfunction "2_2") (pintype "passive"))
      (node (ref "U4") (pin "E6") (pinfunction "VCCBATT_0_E6") (pintype "power_in"))
    )
    (net (code "24") (name "unconnected-(U4F-VCCO_MIO1_501-PadB13)") (class "Default")
      (node (ref "U4") (pin "B13") (pinfunction "VCCO_MIO1_501_B13") (pintype "power_in"))
    )
  )
)
